# uNav44_r1.net
KiCad netlist of a schematic drawn in EAGLE
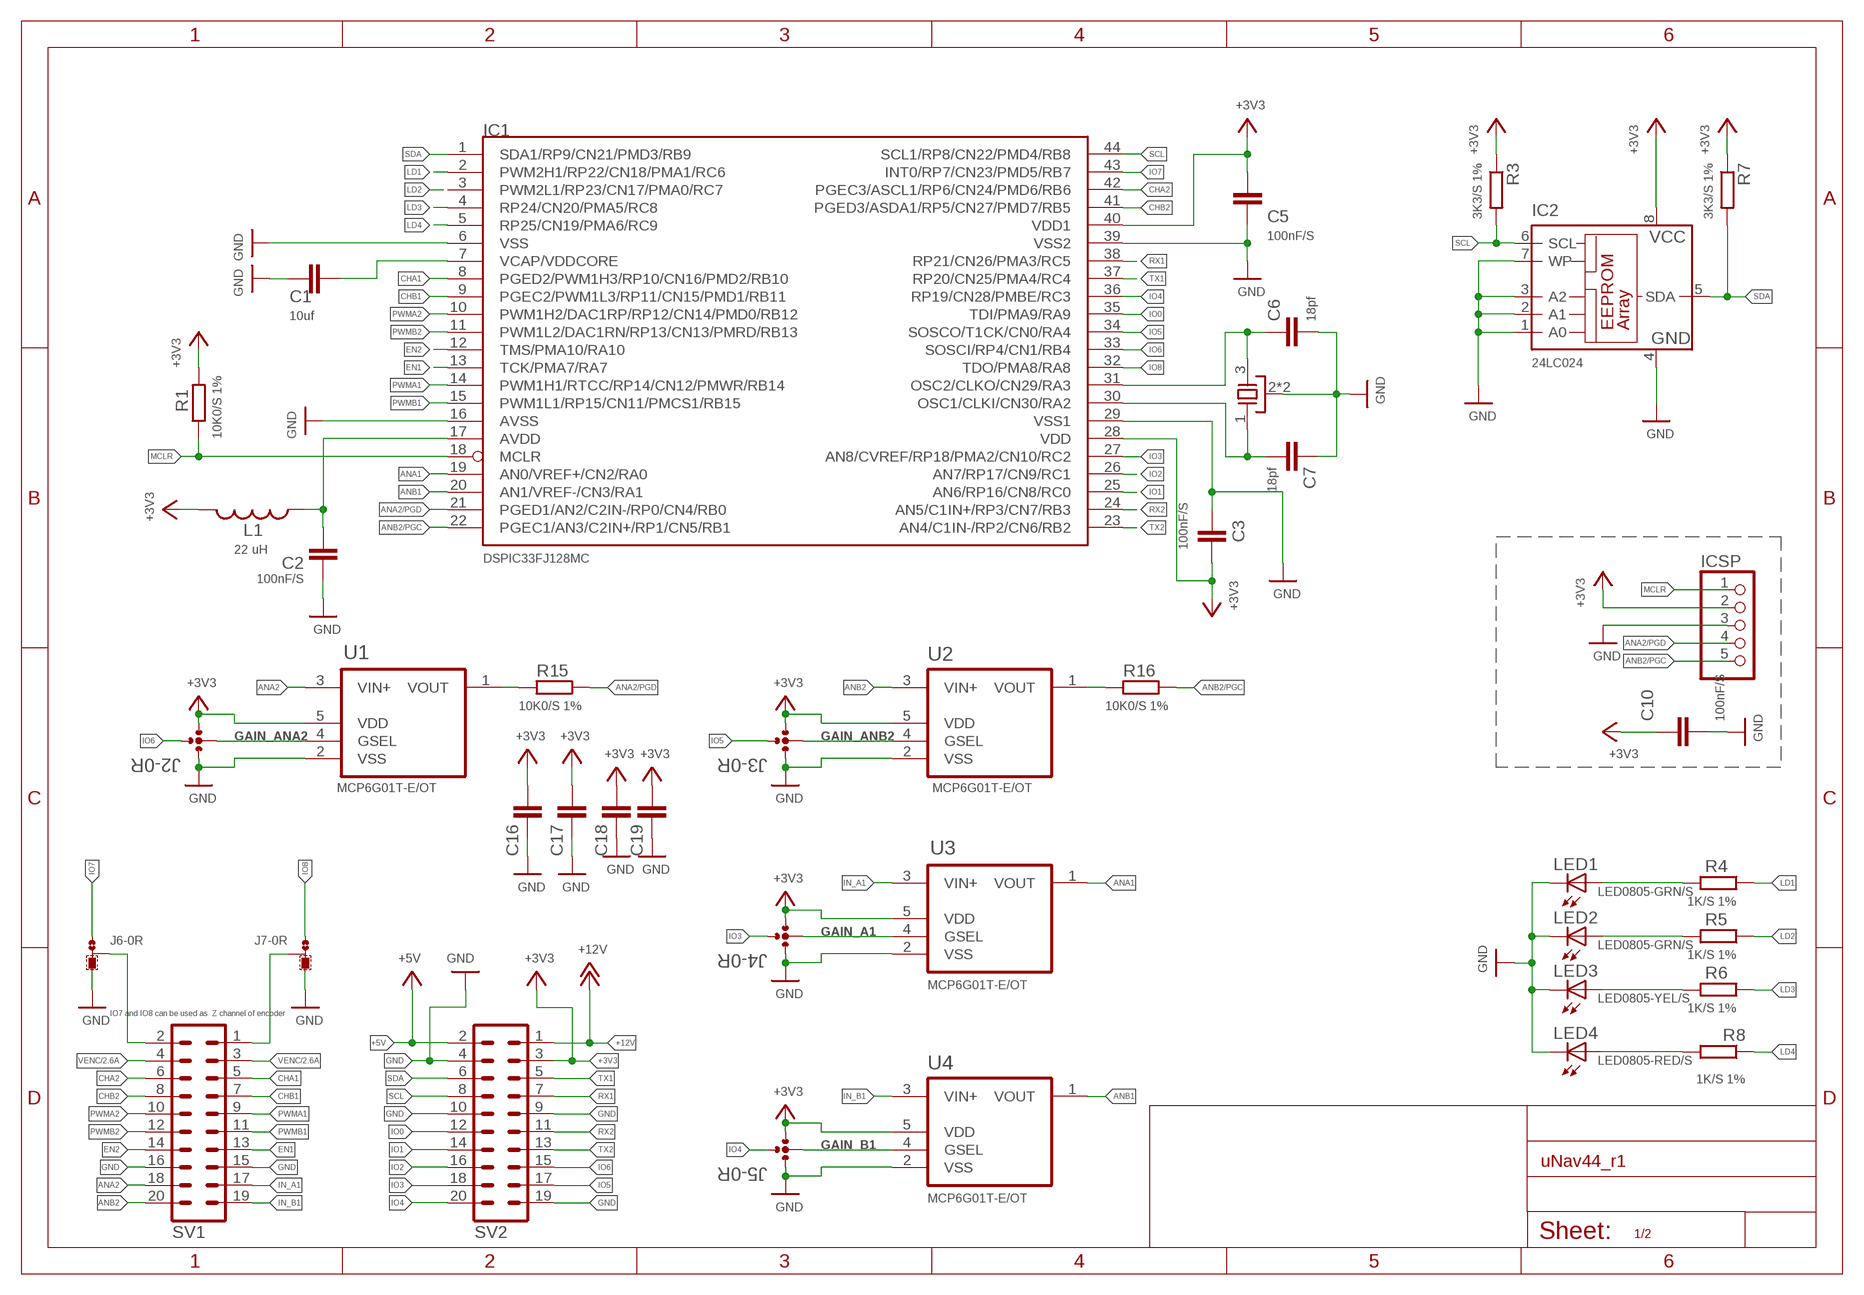
[diagram p0: schematic, sheet 1]
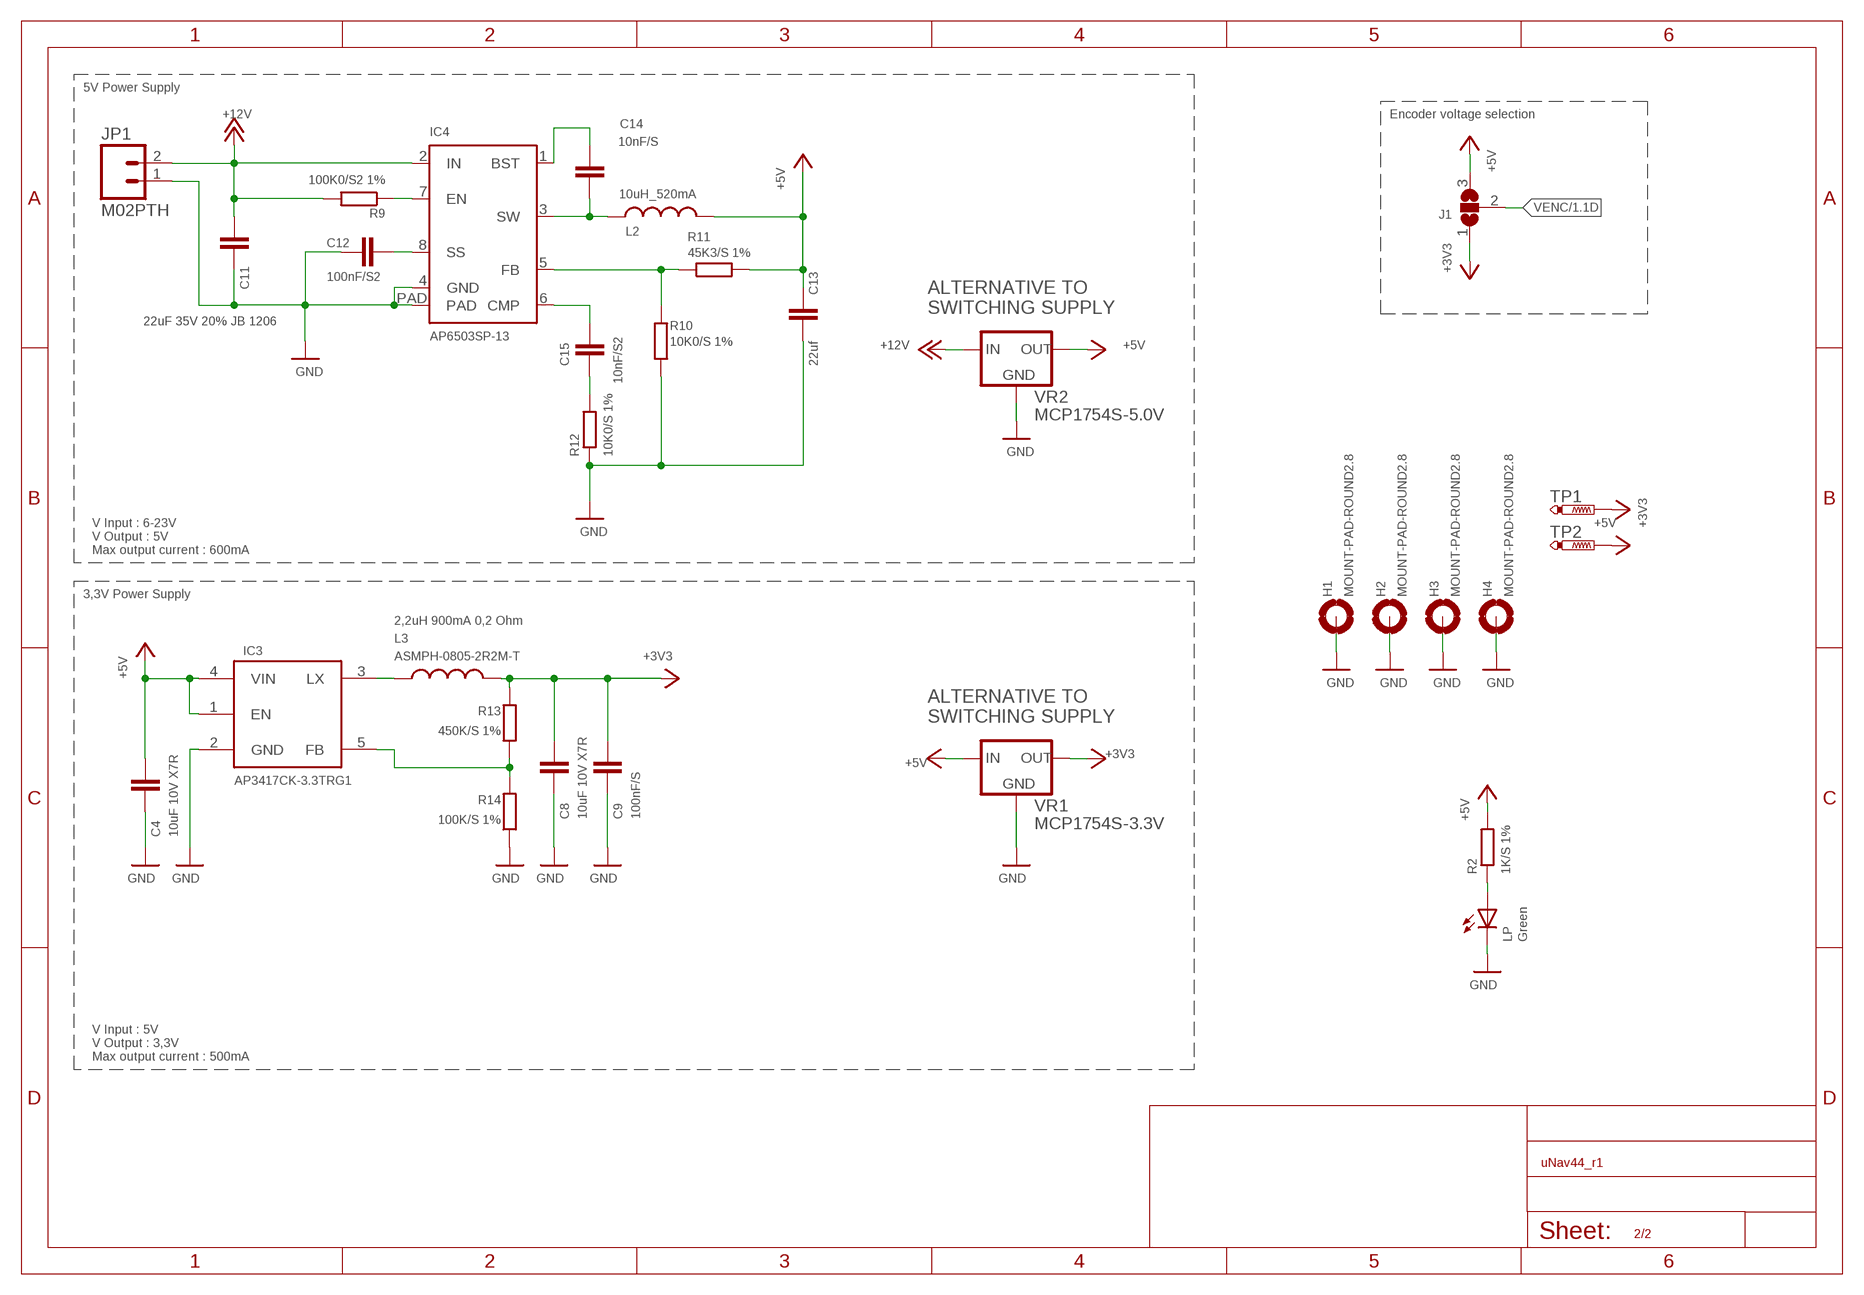
[diagram p1: schematic, sheet 2]

(export (version "E")
  (design (tool "Eeschema 10.0.6"))
  (components
    (comp (ref "C1")
      (value "10uf")
      (footprint "eagle-import:C1206")
      (libsource (lib "eagle-import") (part "C-EUC1206"))
    )
    (comp (ref "C2")
      (value "100nF/S")
      (footprint "eagle-import:C0603")
      (libsource (lib "eagle-import") (part "C-EUC0603"))
    )
    (comp (ref "C3")
      (value "100nF/S")
      (footprint "eagle-import:C0603")
      (libsource (lib "eagle-import") (part "C-EUC0603"))
    )
    (comp (ref "C5")
      (value "100nF/S")
      (footprint "eagle-import:C0603")
      (libsource (lib "eagle-import") (part "C-EUC0603"))
    )
    (comp (ref "C6")
      (value "18pf")
      (footprint "eagle-import:C0603")
      (libsource (lib "eagle-import") (part "C-EUC0603"))
    )
    (comp (ref "C7")
      (value "18pf")
      (footprint "eagle-import:C0603")
      (libsource (lib "eagle-import") (part "C-EUC0603"))
    )
    (comp (ref "C10")
      (value "100nF/S")
      (footprint "eagle-import:C0603")
      (libsource (lib "eagle-import") (part "C-EUC0603"))
    )
    (comp (ref "C16")
      (value "100nF/S")
      (footprint "eagle-import:C0603")
      (libsource (lib "eagle-import") (part "C-EUC0603"))
    )
    (comp (ref "C17")
      (value "100nF/S")
      (footprint "eagle-import:C0603")
      (libsource (lib "eagle-import") (part "C-EUC0603"))
    )
    (comp (ref "C18")
      (value "100nF/S")
      (footprint "eagle-import:C0603")
      (libsource (lib "eagle-import") (part "C-EUC0603"))
    )
    (comp (ref "C19")
      (value "100nF/S")
      (footprint "eagle-import:C0603")
      (libsource (lib "eagle-import") (part "C-EUC0603"))
    )
    (comp (ref "IC1")
      (value "DSPIC33FJ128MC")
      (footprint "eagle-import:TQFP44")
      (libsource (lib "eagle-import") (part "DSPIC33FJ128MC804-PT"))
    )
    (comp (ref "IC2")
      (value "24LC024")
      (footprint "eagle-import:SO-08M")
      (libsource (lib "eagle-import") (part "24SMAA01"))
    )
    (comp (ref "ICSP")
      (value "PINHD-1X05_2.54-S")
      (footprint "eagle-import:1X05-S")
      (libsource (lib "eagle-import") (part "PINHD-1X05_2.54-S"))
    )
    (comp (ref "J2")
      (value "0R-JUMP-4")
      (footprint "eagle-import:C0R-JUMP-4")
      (libsource (lib "eagle-import") (part "0R-JUMP-4"))
    )
    (comp (ref "J3")
      (value "0R-JUMP-4")
      (footprint "eagle-import:C0R-JUMP-4")
      (libsource (lib "eagle-import") (part "0R-JUMP-4"))
    )
    (comp (ref "J4")
      (value "0R-JUMP-4")
      (footprint "eagle-import:C0R-JUMP-4")
      (libsource (lib "eagle-import") (part "0R-JUMP-4"))
    )
    (comp (ref "J5")
      (value "0R-JUMP-4")
      (footprint "eagle-import:C0R-JUMP-4")
      (libsource (lib "eagle-import") (part "0R-JUMP-4"))
    )
    (comp (ref "J6")
      (value "0R-JUMPC")
      (footprint "eagle-import:C0R-JMP")
      (libsource (lib "eagle-import") (part "0R-JUMPC"))
    )
    (comp (ref "J7")
      (value "0R-JUMPC")
      (footprint "eagle-import:C0R-JMP")
      (libsource (lib "eagle-import") (part "0R-JUMPC"))
    )
    (comp (ref "L1")
      (value "22 uH")
      (footprint "eagle-import:0805")
      (libsource (lib "eagle-import") (part "INDUCTOR0805"))
    )
    (comp (ref "LED1")
      (value "LED0805-GRN/S")
      (footprint "eagle-import:CHIPLED_0805")
      (libsource (lib "eagle-import") (part "LEDCHIPLED_0805"))
    )
    (comp (ref "LED2")
      (value "LED0805-GRN/S")
      (footprint "eagle-import:CHIPLED_0805")
      (libsource (lib "eagle-import") (part "LEDCHIPLED_0805"))
    )
    (comp (ref "LED3")
      (value "LED0805-YEL/S")
      (footprint "eagle-import:CHIPLED_0805")
      (libsource (lib "eagle-import") (part "LEDCHIPLED_0805"))
    )
    (comp (ref "LED4")
      (value "LED0805-RED/S")
      (footprint "eagle-import:CHIPLED_0805")
      (libsource (lib "eagle-import") (part "LEDCHIPLED_0805"))
    )
    (comp (ref "R1")
      (value "10K0/S 1%")
      (footprint "eagle-import:R0603")
      (libsource (lib "eagle-import") (part "R-EU_R0603"))
    )
    (comp (ref "R3")
      (value "3K3/S 1%")
      (footprint "eagle-import:R0603")
      (libsource (lib "eagle-import") (part "R-EU_R0603"))
    )
    (comp (ref "R4")
      (value "1K/S 1%")
      (footprint "eagle-import:R0603")
      (libsource (lib "eagle-import") (part "R-EU_R0603"))
    )
    (comp (ref "R5")
      (value "1K/S 1%")
      (footprint "eagle-import:R0603")
      (libsource (lib "eagle-import") (part "R-EU_R0603"))
    )
    (comp (ref "R6")
      (value "1K/S 1%")
      (footprint "eagle-import:R0603")
      (libsource (lib "eagle-import") (part "R-EU_R0603"))
    )
    (comp (ref "R7")
      (value "3K3/S 1%")
      (footprint "eagle-import:R0603")
      (libsource (lib "eagle-import") (part "R-EU_R0603"))
    )
    (comp (ref "R8")
      (value "1K/S 1%")
      (footprint "eagle-import:R0603")
      (libsource (lib "eagle-import") (part "R-EU_R0603"))
    )
    (comp (ref "R15")
      (value "10K0/S 1%")
      (footprint "eagle-import:R0603")
      (libsource (lib "eagle-import") (part "R-EU_R0603"))
    )
    (comp (ref "R16")
      (value "10K0/S 1%")
      (footprint "eagle-import:R0603")
      (libsource (lib "eagle-import") (part "R-EU_R0603"))
    )
    (comp (ref "SV1")
      (value "MA10-2")
      (footprint "eagle-import:MA10-2")
      (fields (field (name "OC_FARNELL") "unknown") (field (name "OC_NEWARK") "unknown"))
      (libsource (lib "eagle-import") (part "MA10-2"))
    )
    (comp (ref "SV2")
      (value "MA10-2")
      (footprint "eagle-import:MA10-2")
      (libsource (lib "eagle-import") (part "MA10-2"))
    )
    (comp (ref "U1")
      (value "MCP6G01T-E/OT")
      (footprint "eagle-import:SOT95P300X145-5N")
      (libsource (lib "eagle-import") (part "MCP6G01T-E/OT"))
    )
    (comp (ref "U2")
      (value "MCP6G01T-E/OT")
      (footprint "eagle-import:SOT95P300X145-5N")
      (libsource (lib "eagle-import") (part "MCP6G01T-E/OT"))
    )
    (comp (ref "U3")
      (value "MCP6G01T-E/OT")
      (footprint "eagle-import:SOT95P300X145-5N")
      (libsource (lib "eagle-import") (part "MCP6G01T-E/OT"))
    )
    (comp (ref "U4")
      (value "MCP6G01T-E/OT")
      (footprint "eagle-import:SOT95P300X145-5N")
      (libsource (lib "eagle-import") (part "MCP6G01T-E/OT"))
    )
    (comp (ref "XT1")
      (value "CTS_32X25_SMD")
      (footprint "eagle-import:CTS_32X25")
      (libsource (lib "eagle-import") (part "CTS_32X25_SMD"))
    )
    (comp (ref "C4")
      (value "10uF 10V X7R")
      (footprint "eagle-import:C0805")
      (libsource (lib "eagle-import") (part "C-EUC0805"))
    )
    (comp (ref "C8")
      (value "10uF 10V X7R")
      (footprint "eagle-import:C0805")
      (libsource (lib "eagle-import") (part "C-EUC0805"))
    )
    (comp (ref "C9")
      (value "100nF/S")
      (footprint "eagle-import:C0603")
      (libsource (lib "eagle-import") (part "C-EUC0603"))
    )
    (comp (ref "C11")
      (value "22uF 35V 20% JB 1206")
      (footprint "eagle-import:C1206")
      (libsource (lib "eagle-import") (part "C-EUC1206"))
    )
    (comp (ref "C12")
      (value "100nF/S2")
      (footprint "eagle-import:C0603")
      (libsource (lib "eagle-import") (part "C-EUC0603"))
    )
    (comp (ref "C13")
      (value "22uf")
      (footprint "eagle-import:C1206")
      (libsource (lib "eagle-import") (part "C-EUC1206"))
    )
    (comp (ref "C14")
      (value "10nF/S")
      (footprint "eagle-import:C0603")
      (libsource (lib "eagle-import") (part "C-EUC0603"))
    )
    (comp (ref "C15")
      (value "10nF/S2")
      (footprint "eagle-import:C0603")
      (libsource (lib "eagle-import") (part "C-EUC0603"))
    )
    (comp (ref "H1")
      (value "MOUNT-PAD-ROUND2.8")
      (footprint "eagle-import:2,8-PAD")
      (libsource (lib "eagle-import") (part "MOUNT-PAD-ROUND2.8"))
    )
    (comp (ref "H2")
      (value "MOUNT-PAD-ROUND2.8")
      (footprint "eagle-import:2,8-PAD")
      (libsource (lib "eagle-import") (part "MOUNT-PAD-ROUND2.8"))
    )
    (comp (ref "H3")
      (value "MOUNT-PAD-ROUND2.8")
      (footprint "eagle-import:2,8-PAD")
      (libsource (lib "eagle-import") (part "MOUNT-PAD-ROUND2.8"))
    )
    (comp (ref "H4")
      (value "MOUNT-PAD-ROUND2.8")
      (footprint "eagle-import:2,8-PAD")
      (libsource (lib "eagle-import") (part "MOUNT-PAD-ROUND2.8"))
    )
    (comp (ref "IC3")
      (value "AP3417CK-3.3TRG1")
      (footprint "eagle-import:SOT-23-5")
      (libsource (lib "eagle-import") (part "AP3417CSOT-23-5"))
    )
    (comp (ref "IC4")
      (value "AP6503SP-13")
      (footprint "eagle-import:SO-8EP")
      (libsource (lib "eagle-import") (part "AP6503SP-13'SO-8EP'"))
    )
    (comp (ref "J1")
      (value "SJ2W")
      (footprint "eagle-import:SJ_2")
      (libsource (lib "eagle-import") (part "SJ2W"))
    )
    (comp (ref "JP1")
      (value "M02PTH")
      (footprint "eagle-import:1X02")
      (libsource (lib "eagle-import") (part "M02PTH"))
    )
    (comp (ref "L2")
      (value "10uH_520mA")
      (footprint "eagle-import:1210")
      (libsource (lib "eagle-import") (part "INDUCTOR1210"))
    )
    (comp (ref "L3")
      (value "ASMPH-0805-2R2M-T")
      (footprint "eagle-import:0805")
      (libsource (lib "eagle-import") (part "INDUCTOR0805"))
    )
    (comp (ref "LP")
      (value "Green")
      (footprint "eagle-import:CHIPLED_0805")
      (libsource (lib "eagle-import") (part "LEDCHIPLED_0805"))
    )
    (comp (ref "R2")
      (value "1K/S 1%")
      (footprint "eagle-import:R0603")
      (libsource (lib "eagle-import") (part "R-EU_R0603"))
    )
    (comp (ref "R9")
      (value "100K0/S2 1%")
      (footprint "eagle-import:R0603")
      (libsource (lib "eagle-import") (part "R-EU_R0603"))
    )
    (comp (ref "R10")
      (value "10K0/S 1%")
      (footprint "eagle-import:R0603")
      (libsource (lib "eagle-import") (part "R-EU_R0603"))
    )
    (comp (ref "R11")
      (value "45K3/S 1%")
      (footprint "eagle-import:R0603")
      (libsource (lib "eagle-import") (part "R-EU_R0603"))
    )
    (comp (ref "R12")
      (value "10K0/S 1%")
      (footprint "eagle-import:R0603")
      (libsource (lib "eagle-import") (part "R-EU_R0603"))
    )
    (comp (ref "R13")
      (value "450K/S 1%")
      (footprint "eagle-import:R0603")
      (libsource (lib "eagle-import") (part "R-EU_R0603"))
    )
    (comp (ref "R14")
      (value "100K/S 1%")
      (footprint "eagle-import:R0603")
      (libsource (lib "eagle-import") (part "R-EU_R0603"))
    )
    (comp (ref "TP1")
      (value "PTR1TP07R")
      (footprint "eagle-import:TP07R")
      (libsource (lib "eagle-import") (part "PTR1TP07R"))
    )
    (comp (ref "TP2")
      (value "PTR1TP07R")
      (footprint "eagle-import:TP07R")
      (libsource (lib "eagle-import") (part "PTR1TP07R"))
    )
    (comp (ref "VR1")
      (value "MCP1754S-3.3V")
      (footprint "eagle-import:SOT89")
      (libsource (lib "eagle-import") (part "MCP1754S"))
    )
    (comp (ref "VR2")
      (value "MCP1754S-5.0V")
      (footprint "eagle-import:SOT89")
      (libsource (lib "eagle-import") (part "MCP1754S"))
    )
  )
  (nets
    (net (code "1") (name "+3V3") (class "Default")
      (node (ref "C10") (pin "1") (pinfunction "1_1") (pintype "passive"))
      (node (ref "C16") (pin "1") (pinfunction "1_1") (pintype "passive"))
      (node (ref "C17") (pin "1") (pinfunction "1_1") (pintype "passive"))
      (node (ref "C18") (pin "1") (pinfunction "1_1") (pintype "passive"))
      (node (ref "C19") (pin "1") (pinfunction "1_1") (pintype "passive"))
      (node (ref "C3") (pin "1") (pinfunction "1_1") (pintype "passive"))
      (node (ref "C5") (pin "2") (pinfunction "2_2") (pintype "passive"))
      (node (ref "C8") (pin "1") (pinfunction "1_1") (pintype "passive"))
      (node (ref "C9") (pin "1") (pinfunction "1_1") (pintype "passive"))
      (node (ref "IC1") (pin "28") (pinfunction "VDD_28") (pintype "power_in"))
      (node (ref "IC1") (pin "40") (pinfunction "VDD1_40") (pintype "power_in"))
      (node (ref "IC2") (pin "8") (pinfunction "VCC_8") (pintype "power_in"))
      (node (ref "ICSP") (pin "2") (pinfunction "2_2") (pintype "passive"))
      (node (ref "J1") (pin "1") (pinfunction "1_1") (pintype "passive"))
      (node (ref "J2") (pin "1") (pinfunction "1_1") (pintype "passive"))
      (node (ref "J3") (pin "1") (pinfunction "1_1") (pintype "passive"))
      (node (ref "J4") (pin "1") (pinfunction "1_1") (pintype "passive"))
      (node (ref "J5") (pin "1") (pinfunction "1_1") (pintype "passive"))
      (node (ref "L1") (pin "2") (pinfunction "2_2") (pintype "passive"))
      (node (ref "L3") (pin "2") (pinfunction "2_2") (pintype "passive"))
      (node (ref "R1") (pin "2") (pinfunction "2_2") (pintype "passive"))
      (node (ref "R13") (pin "2") (pinfunction "2_2") (pintype "passive"))
      (node (ref "R3") (pin "1") (pinfunction "1_1") (pintype "passive"))
      (node (ref "R7") (pin "1") (pinfunction "1_1") (pintype "passive"))
      (node (ref "SV2") (pin "3") (pinfunction "3_3") (pintype "passive"))
      (node (ref "TP1") (pin "TP") (pinfunction "TP_TP") (pintype "input"))
      (node (ref "U1") (pin "5") (pinfunction "VDD_5") (pintype "power_in"))
      (node (ref "U2") (pin "5") (pinfunction "VDD_5") (pintype "power_in"))
      (node (ref "U3") (pin "5") (pinfunction "VDD_5") (pintype "power_in"))
      (node (ref "U4") (pin "5") (pinfunction "VDD_5") (pintype "power_in"))
      (node (ref "VR1") (pin "3") (pinfunction "OUT_3") (pintype "passive"))
    )
    (net (code "2") (name "+5V") (class "Default")
      (node (ref "C13") (pin "1") (pinfunction "1_1") (pintype "passive"))
      (node (ref "C4") (pin "1") (pinfunction "1_1") (pintype "passive"))
      (node (ref "IC3") (pin "1") (pinfunction "EN_1") (pintype "bidirectional"))
      (node (ref "IC3") (pin "4") (pinfunction "VIN_4") (pintype "bidirectional"))
      (node (ref "J1") (pin "3") (pinfunction "3_3") (pintype "passive"))
      (node (ref "L2") (pin "2") (pinfunction "2_2") (pintype "passive"))
      (node (ref "R11") (pin "2") (pinfunction "2_2") (pintype "passive"))
      (node (ref "R2") (pin "2") (pinfunction "2_2") (pintype "passive"))
      (node (ref "SV2") (pin "2") (pinfunction "2_2") (pintype "passive"))
      (node (ref "TP2") (pin "TP") (pinfunction "TP_TP") (pintype "input"))
      (node (ref "VR1") (pin "1") (pinfunction "IN_1") (pintype "input"))
      (node (ref "VR2") (pin "3") (pinfunction "OUT_3") (pintype "passive"))
    )
    (net (code "3") (name "+12V") (class "Default")
      (node (ref "C11") (pin "1") (pinfunction "1_1") (pintype "passive"))
      (node (ref "IC4") (pin "2") (pinfunction "IN_2") (pintype "power_in"))
      (node (ref "JP1") (pin "2") (pinfunction "2_2") (pintype "passive"))
      (node (ref "R9") (pin "2") (pinfunction "2_2") (pintype "passive"))
      (node (ref "SV2") (pin "1") (pinfunction "1_1") (pintype "passive"))
      (node (ref "VR2") (pin "1") (pinfunction "IN_1") (pintype "input"))
    )
    (net (code "4") (name "ANA1") (class "Default")
      (node (ref "IC1") (pin "19") (pinfunction "AN0/VREF+/CN2/RA0_19") (pintype "bidirectional"))
      (node (ref "U3") (pin "1") (pinfunction "VOUT_1") (pintype "output"))
    )
    (net (code "5") (name "ANA2") (class "Default")
      (node (ref "SV1") (pin "18") (pinfunction "18_18") (pintype "passive"))
      (node (ref "U1") (pin "3") (pinfunction "VIN+_3") (pintype "input"))
    )
    (net (code "6") (name "ANA2{slash}PGD") (class "Default")
      (node (ref "IC1") (pin "21") (pinfunction "PGED1/AN2/C2IN-/RP0/CN4/RB0_21") (pintype "bidirectional"))
      (node (ref "ICSP") (pin "4") (pinfunction "4_4") (pintype "passive"))
      (node (ref "R15") (pin "1") (pinfunction "1_1") (pintype "passive"))
    )
    (net (code "7") (name "ANB1") (class "Default")
      (node (ref "IC1") (pin "20") (pinfunction "AN1/VREF-/CN3/RA1_20") (pintype "bidirectional"))
      (node (ref "U4") (pin "1") (pinfunction "VOUT_1") (pintype "output"))
    )
    (net (code "8") (name "ANB2") (class "Default")
      (node (ref "SV1") (pin "20") (pinfunction "20_20") (pintype "passive"))
      (node (ref "U2") (pin "3") (pinfunction "VIN+_3") (pintype "input"))
    )
    (net (code "9") (name "ANB2{slash}PGC") (class "Default")
      (node (ref "IC1") (pin "22") (pinfunction "PGEC1/AN3/C2IN+/RP1/CN5/RB1_22") (pintype "bidirectional"))
      (node (ref "ICSP") (pin "5") (pinfunction "5_5") (pintype "passive"))
      (node (ref "R16") (pin "1") (pinfunction "1_1") (pintype "passive"))
    )
    (net (code "10") (name "CHA1") (class "Default")
      (node (ref "IC1") (pin "8") (pinfunction "PGED2/PWM1H3/RP10/CN16/PMD2/RB10_8") (pintype "bidirectional"))
      (node (ref "SV1") (pin "5") (pinfunction "5_5") (pintype "passive"))
    )
    (net (code "11") (name "CHA2") (class "Default")
      (node (ref "IC1") (pin "42") (pinfunction "PGEC3/ASCL1/RP6/CN24/PMD6/RB6_42") (pintype "bidirectional"))
      (node (ref "SV1") (pin "6") (pinfunction "6_6") (pintype "passive"))
    )
    (net (code "12") (name "CHB1") (class "Default")
      (node (ref "IC1") (pin "9") (pinfunction "PGEC2/PWM1L3/RP11/CN15/PMD1/RB11_9") (pintype "bidirectional"))
      (node (ref "SV1") (pin "7") (pinfunction "7_7") (pintype "passive"))
    )
    (net (code "13") (name "CHB2") (class "Default")
      (node (ref "IC1") (pin "41") (pinfunction "PGED3/ASDA1/RP5/CN27/PMD7/RB5_41") (pintype "bidirectional"))
      (node (ref "SV1") (pin "8") (pinfunction "8_8") (pintype "passive"))
    )
    (net (code "14") (name "EN1") (class "Default")
      (node (ref "IC1") (pin "13") (pinfunction "TCK/PMA7/RA7_13") (pintype "bidirectional"))
      (node (ref "SV1") (pin "13") (pinfunction "13_13") (pintype "passive"))
    )
    (net (code "15") (name "EN2") (class "Default")
      (node (ref "IC1") (pin "12") (pinfunction "TMS/PMA10/RA10_12") (pintype "bidirectional"))
      (node (ref "SV1") (pin "14") (pinfunction "14_14") (pintype "passive"))
    )
    (net (code "16") (name "GAIN_A1") (class "Default")
      (node (ref "J4") (pin "2") (pinfunction "2_2") (pintype "passive"))
      (node (ref "U3") (pin "4") (pinfunction "GSEL_4") (pintype "input"))
    )
    (net (code "17") (name "GAIN_ANA2") (class "Default")
      (node (ref "J2") (pin "2") (pinfunction "2_2") (pintype "passive"))
      (node (ref "U1") (pin "4") (pinfunction "GSEL_4") (pintype "input"))
    )
    (net (code "18") (name "GAIN_ANB2") (class "Default")
      (node (ref "J3") (pin "2") (pinfunction "2_2") (pintype "passive"))
      (node (ref "U2") (pin "4") (pinfunction "GSEL_4") (pintype "input"))
    )
    (net (code "19") (name "GAIN_B1") (class "Default")
      (node (ref "J5") (pin "2") (pinfunction "2_2") (pintype "passive"))
      (node (ref "U4") (pin "4") (pinfunction "GSEL_4") (pintype "input"))
    )
    (net (code "20") (name "GND") (class "Default")
      (node (ref "C1") (pin "2") (pinfunction "2_2") (pintype "passive"))
      (node (ref "C10") (pin "2") (pinfunction "2_2") (pintype "passive"))
      (node (ref "C11") (pin "2") (pinfunction "2_2") (pintype "passive"))
      (node (ref "C12") (pin "2") (pinfunction "2_2") (pintype "passive"))
      (node (ref "C13") (pin "2") (pinfunction "2_2") (pintype "passive"))
      (node (ref "C16") (pin "2") (pinfunction "2_2") (pintype "passive"))
      (node (ref "C17") (pin "2") (pinfunction "2_2") (pintype "passive"))
      (node (ref "C18") (pin "2") (pinfunction "2_2") (pintype "passive"))
      (node (ref "C19") (pin "2") (pinfunction "2_2") (pintype "passive"))
      (node (ref "C2") (pin "1") (pinfunction "1_1") (pintype "passive"))
      (node (ref "C3") (pin "2") (pinfunction "2_2") (pintype "passive"))
      (node (ref "C4") (pin "2") (pinfunction "2_2") (pintype "passive"))
      (node (ref "C5") (pin "1") (pinfunction "1_1") (pintype "passive"))
      (node (ref "C6") (pin "2") (pinfunction "2_2") (pintype "passive"))
      (node (ref "C7") (pin "1") (pinfunction "1_1") (pintype "passive"))
      (node (ref "C8") (pin "2") (pinfunction "2_2") (pintype "passive"))
      (node (ref "C9") (pin "2") (pinfunction "2_2") (pintype "passive"))
      (node (ref "H1") (pin "B2,8") (pinfunction "MOUNT_B2,8") (pintype "passive"))
      (node (ref "H2") (pin "B2,8") (pinfunction "MOUNT_B2,8") (pintype "passive"))
      (node (ref "H3") (pin "B2,8") (pinfunction "MOUNT_B2,8") (pintype "passive"))
      (node (ref "H4") (pin "B2,8") (pinfunction "MOUNT_B2,8") (pintype "passive"))
      (node (ref "IC1") (pin "16") (pinfunction "AVSS_16") (pintype "power_in"))
      (node (ref "IC1") (pin "29") (pinfunction "VSS1_29") (pintype "power_in"))
      (node (ref "IC1") (pin "39") (pinfunction "VSS2_39") (pintype "power_in"))
      (node (ref "IC1") (pin "6") (pinfunction "VSS_6") (pintype "power_in"))
      (node (ref "IC2") (pin "1") (pinfunction "A0_1") (pintype "input"))
      (node (ref "IC2") (pin "2") (pinfunction "A1_2") (pintype "input"))
      (node (ref "IC2") (pin "3") (pinfunction "A2_3") (pintype "input"))
      (node (ref "IC2") (pin "4") (pinfunction "GND_4") (pintype "power_in"))
      (node (ref "IC2") (pin "7") (pinfunction "WP_7") (pintype "input"))
      (node (ref "IC3") (pin "2") (pinfunction "GND_2") (pintype "bidirectional"))
      (node (ref "IC4") (pin "4") (pinfunction "GND_4") (pintype "power_in"))
      (node (ref "IC4") (pin "PAD") (pinfunction "PAD_PAD") (pintype "power_in"))
      (node (ref "ICSP") (pin "3") (pinfunction "3_3") (pintype "passive"))
      (node (ref "J2") (pin "3") (pinfunction "3_3") (pintype "passive"))
      (node (ref "J3") (pin "3") (pinfunction "3_3") (pintype "passive"))
      (node (ref "J4") (pin "3") (pinfunction "3_3") (pintype "passive"))
      (node (ref "J5") (pin "3") (pinfunction "3_3") (pintype "passive"))
      (node (ref "J6") (pin "3") (pinfunction "3_3") (pintype "passive"))
      (node (ref "J7") (pin "3") (pinfunction "3_3") (pintype "passive"))
      (node (ref "JP1") (pin "1") (pinfunction "1_1") (pintype "passive"))
      (node (ref "LED1") (pin "C") (pinfunction "C_C") (pintype "passive"))
      (node (ref "LED2") (pin "C") (pinfunction "C_C") (pintype "passive"))
      (node (ref "LED3") (pin "C") (pinfunction "C_C") (pintype "passive"))
      (node (ref "LED4") (pin "C") (pinfunction "C_C") (pintype "passive"))
      (node (ref "LP") (pin "C") (pinfunction "C_C") (pintype "passive"))
      (node (ref "R10") (pin "2") (pinfunction "2_2") (pintype "passive"))
      (node (ref "R12") (pin "1") (pinfunction "1_1") (pintype "passive"))
      (node (ref "R14") (pin "1") (pinfunction "1_1") (pintype "passive"))
      (node (ref "SV1") (pin "15") (pinfunction "15_15") (pintype "passive"))
      (node (ref "SV1") (pin "16") (pinfunction "16_16") (pintype "passive"))
      (node (ref "SV2") (pin "10") (pinfunction "10_10") (pintype "passive"))
      (node (ref "SV2") (pin "19") (pinfunction "19_19") (pintype "passive"))
      (node (ref "SV2") (pin "4") (pinfunction "4_4") (pintype "passive"))
      (node (ref "SV2") (pin "9") (pinfunction "9_9") (pintype "passive"))
      (node (ref "U1") (pin "2") (pinfunction "VSS_2") (pintype "passive"))
      (node (ref "U2") (pin "2") (pinfunction "VSS_2") (pintype "passive"))
      (node (ref "U3") (pin "2") (pinfunction "VSS_2") (pintype "passive"))
      (node (ref "U4") (pin "2") (pinfunction "VSS_2") (pintype "passive"))
      (node (ref "VR1") (pin "2") (pinfunction "GND_2") (pintype "input"))
      (node (ref "VR1") (pin "4") (pinfunction "GND_4") (pintype "input"))
      (node (ref "VR2") (pin "2") (pinfunction "GND_2") (pintype "input"))
      (node (ref "VR2") (pin "4") (pinfunction "GND_4") (pintype "input"))
      (node (ref "XT1") (pin "2") (pinfunction "GND_2") (pintype "power_in"))
      (node (ref "XT1") (pin "4") (pinfunction "GND_4") (pintype "power_in"))
    )
    (net (code "21") (name "IN_A1") (class "Default")
      (node (ref "SV1") (pin "17") (pinfunction "17_17") (pintype "passive"))
      (node (ref "U3") (pin "3") (pinfunction "VIN+_3") (pintype "input"))
    )
    (net (code "22") (name "IN_B1") (class "Default")
      (node (ref "SV1") (pin "19") (pinfunction "19_19") (pintype "passive"))
      (node (ref "U4") (pin "3") (pinfunction "VIN+_3") (pintype "input"))
    )
    (net (code "23") (name "IO0") (class "Default")
      (node (ref "IC1") (pin "35") (pinfunction "TDI/PMA9/RA9_35") (pintype "bidirectional"))
      (node (ref "SV2") (pin "12") (pinfunction "12_12") (pintype "passive"))
    )
    (net (code "24") (name "IO1") (class "Default")
      (node (ref "IC1") (pin "25") (pinfunction "AN6/RP16/CN8/RC0_25") (pintype "bidirectional"))
      (node (ref "SV2") (pin "14") (pinfunction "14_14") (pintype "passive"))
    )
    (net (code "25") (name "IO2") (class "Default")
      (node (ref "IC1") (pin "26") (pinfunction "AN7/RP17/CN9/RC1_26") (pintype "bidirectional"))
      (node (ref "SV2") (pin "16") (pinfunction "16_16") (pintype "passive"))
    )
    (net (code "26") (name "IO3") (class "Default")
      (node (ref "IC1") (pin "27") (pinfunction "AN8/CVREF/RP18/PMA2/CN10/RC2_27") (pintype "bidirectional"))
      (node (ref "J4") (pin "4") (pinfunction "4_4") (pintype "passive"))
      (node (ref "SV2") (pin "18") (pinfunction "18_18") (pintype "passive"))
    )
    (net (code "27") (name "IO4") (class "Default")
      (node (ref "IC1") (pin "36") (pinfunction "RP19/CN28/PMBE/RC3_36") (pintype "bidirectional"))
      (node (ref "J5") (pin "4") (pinfunction "4_4") (pintype "passive"))
      (node (ref "SV2") (pin "20") (pinfunction "20_20") (pintype "passive"))
    )
    (net (code "28") (name "IO5") (class "Default")
      (node (ref "IC1") (pin "34") (pinfunction "SOSCO/T1CK/CN0/RA4_34") (pintype "bidirectional"))
      (node (ref "J3") (pin "4") (pinfunction "4_4") (pintype "passive"))
      (node (ref "SV2") (pin "17") (pinfunction "17_17") (pintype "passive"))
    )
    (net (code "29") (name "IO6") (class "Default")
      (node (ref "IC1") (pin "33") (pinfunction "SOSCI/RP4/CN1/RB4_33") (pintype "bidirectional"))
      (node (ref "J2") (pin "4") (pinfunction "4_4") (pintype "passive"))
      (node (ref "SV2") (pin "15") (pinfunction "15_15") (pintype "passive"))
    )
    (net (code "30") (name "IO7") (class "Default")
      (node (ref "IC1") (pin "43") (pinfunction "INT0/RP7/CN23/PMD5/RB7_43") (pintype "bidirectional"))
      (node (ref "J6") (pin "1") (pinfunction "1_1") (pintype "passive"))
    )
    (net (code "31") (name "IO8") (class "Default")
      (node (ref "IC1") (pin "32") (pinfunction "TDO/PMA8/RA8_32") (pintype "bidirectional"))
      (node (ref "J7") (pin "1") (pinfunction "1_1") (pintype "passive"))
    )
    (net (code "32") (name "LD1") (class "Default")
      (node (ref "IC1") (pin "2") (pinfunction "PWM2H1/RP22/CN18/PMA1/RC6_2") (pintype "bidirectional"))
      (node (ref "R4") (pin "1") (pinfunction "1_1") (pintype "passive"))
    )
    (net (code "33") (name "LD2") (class "Default")
      (node (ref "IC1") (pin "3") (pinfunction "PWM2L1/RP23/CN17/PMA0/RC7_3") (pintype "bidirectional"))
      (node (ref "R5") (pin "1") (pinfunction "1_1") (pintype "passive"))
    )
    (net (code "34") (name "LD3") (class "Default")
      (node (ref "IC1") (pin "4") (pinfunction "RP24/CN20/PMA5/RC8_4") (pintype "bidirectional"))
      (node (ref "R6") (pin "1") (pinfunction "1_1") (pintype "passive"))
    )
    (net (code "35") (name "LD4") (class "Default")
      (node (ref "IC1") (pin "5") (pinfunction "RP25/CN19/PMA6/RC9_5") (pintype "bidirectional"))
      (node (ref "R8") (pin "1") (pinfunction "1_1") (pintype "passive"))
    )
    (net (code "36") (name "MCLR") (class "Default")
      (node (ref "IC1") (pin "18") (pinfunction "MCLR_18") (pintype "input"))
      (node (ref "ICSP") (pin "1") (pinfunction "1_1") (pintype "passive"))
      (node (ref "R1") (pin "1") (pinfunction "1_1") (pintype "passive"))
    )
    (net (code "37") (name "Net-(C15-Pad2)") (class "Default")
      (node (ref "C15") (pin "2") (pinfunction "2_2") (pintype "passive"))
      (node (ref "R12") (pin "2") (pinfunction "2_2") (pintype "passive"))
    )
    (net (code "38") (name "Net-(IC1-AVDD)") (class "Default")
      (node (ref "C2") (pin "2") (pinfunction "2_2") (pintype "passive"))
      (node (ref "IC1") (pin "17") (pinfunction "AVDD_17") (pintype "power_in"))
      (node (ref "L1") (pin "1") (pinfunction "1_1") (pintype "passive"))
    )
    (net (code "39") (name "Net-(IC1-OSC1{slash}CLKI{slash}CN30{slash}RA2)") (class "Default")
      (node (ref "C7") (pin "2") (pinfunction "2_2") (pintype "passive"))
      (node (ref "IC1") (pin "30") (pinfunction "OSC1/CLKI/CN30/RA2_30") (pintype "bidirectional"))
      (node (ref "XT1") (pin "1") (pinfunction "X1_1") (pintype "bidirectional"))
    )
    (net (code "40") (name "Net-(IC1-OSC2{slash}CLKO{slash}CN29{slash}RA3)") (class "Default")
      (node (ref "C6") (pin "1") (pinfunction "1_1") (pintype "passive"))
      (node (ref "IC1") (pin "31") (pinfunction "OSC2/CLKO/CN29/RA3_31") (pintype "bidirectional"))
      (node (ref "XT1") (pin "3") (pinfunction "X2_3") (pintype "bidirectional"))
    )
    (net (code "41") (name "Net-(IC1-VCAP{slash}VDDCORE)") (class "Default")
      (node (ref "C1") (pin "1") (pinfunction "1_1") (pintype "passive"))
      (node (ref "IC1") (pin "7") (pinfunction "VCAP/VDDCORE_7") (pintype "power_in"))
    )
    (net (code "42") (name "Net-(IC3-FB)") (class "Default")
      (node (ref "IC3") (pin "5") (pinfunction "FB_5") (pintype "bidirectional"))
      (node (ref "R13") (pin "1") (pinfunction "1_1") (pintype "passive"))
      (node (ref "R14") (pin "2") (pinfunction "2_2") (pintype "passive"))
    )
    (net (code "43") (name "Net-(IC3-LX)") (class "Default")
      (node (ref "IC3") (pin "3") (pinfunction "LX_3") (pintype "bidirectional"))
      (node (ref "L3") (pin "1") (pinfunction "1_1") (pintype "passive"))
    )
    (net (code "44") (name "Net-(IC4-BST)") (class "Default")
      (node (ref "C14") (pin "1") (pinfunction "1_1") (pintype "passive"))
      (node (ref "IC4") (pin "1") (pinfunction "BST_1") (pintype "bidirectional"))
    )
    (net (code "45") (name "Net-(IC4-CMP)") (class "Default")
      (node (ref "C15") (pin "1") (pinfunction "1_1") (pintype "passive"))
      (node (ref "IC4") (pin "6") (pinfunction "CMP_6") (pintype "bidirectional"))
    )
    (net (code "46") (name "Net-(IC4-EN)") (class "Default")
      (node (ref "IC4") (pin "7") (pinfunction "EN_7") (pintype "bidirectional"))
      (node (ref "R9") (pin "1") (pinfunction "1_1") (pintype "passive"))
    )
    (net (code "47") (name "Net-(IC4-FB)") (class "Default")
      (node (ref "IC4") (pin "5") (pinfunction "FB_5") (pintype "bidirectional"))
      (node (ref "R10") (pin "1") (pinfunction "1_1") (pintype "passive"))
      (node (ref "R11") (pin "1") (pinfunction "1_1") (pintype "passive"))
    )
    (net (code "48") (name "Net-(IC4-SS)") (class "Default")
      (node (ref "C12") (pin "1") (pinfunction "1_1") (pintype "passive"))
      (node (ref "IC4") (pin "8") (pinfunction "SS_8") (pintype "bidirectional"))
    )
    (net (code "49") (name "Net-(IC4-SW)") (class "Default")
      (node (ref "C14") (pin "2") (pinfunction "2_2") (pintype "passive"))
      (node (ref "IC4") (pin "3") (pinfunction "SW_3") (pintype "bidirectional"))
      (node (ref "L2") (pin "1") (pinfunction "1_1") (pintype "passive"))
    )
    (net (code "50") (name "Net-(J6-Pad2)") (class "Default")
      (node (ref "J6") (pin "2") (pinfunction "2_2") (pintype "passive"))
      (node (ref "SV1") (pin "2") (pinfunction "2_2") (pintype "passive"))
    )
    (net (code "51") (name "Net-(J7-Pad2)") (class "Default")
      (node (ref "J7") (pin "2") (pinfunction "2_2") (pintype "passive"))
      (node (ref "SV1") (pin "1") (pinfunction "1_1") (pintype "passive"))
    )
    (net (code "52") (name "Net-(LED1-PadA)") (class "Default")
      (node (ref "LED1") (pin "A") (pinfunction "A_A") (pintype "passive"))
      (node (ref "R4") (pin "2") (pinfunction "2_2") (pintype "passive"))
    )
    (net (code "53") (name "Net-(LED2-PadA)") (class "Default")
      (node (ref "LED2") (pin "A") (pinfunction "A_A") (pintype "passive"))
      (node (ref "R5") (pin "2") (pinfunction "2_2") (pintype "passive"))
    )
    (net (code "54") (name "Net-(LED3-PadA)") (class "Default")
      (node (ref "LED3") (pin "A") (pinfunction "A_A") (pintype "passive"))
      (node (ref "R6") (pin "2") (pinfunction "2_2") (pintype "passive"))
    )
    (net (code "55") (name "Net-(LED4-PadA)") (class "Default")
      (node (ref "LED4") (pin "A") (pinfunction "A_A") (pintype "passive"))
      (node (ref "R8") (pin "2") (pinfunction "2_2") (pintype "passive"))
    )
    (net (code "56") (name "Net-(LP-PadA)") (class "Default")
      (node (ref "LP") (pin "A") (pinfunction "A_A") (pintype "passive"))
      (node (ref "R2") (pin "1") (pinfunction "1_1") (pintype "passive"))
    )
    (net (code "57") (name "Net-(U1-VOUT)") (class "Default")
      (node (ref "R15") (pin "2") (pinfunction "2_2") (pintype "passive"))
      (node (ref "U1") (pin "1") (pinfunction "VOUT_1") (pintype "output"))
    )
    (net (code "58") (name "Net-(U2-VOUT)") (class "Default")
      (node (ref "R16") (pin "2") (pinfunction "2_2") (pintype "passive"))
      (node (ref "U2") (pin "1") (pinfunction "VOUT_1") (pintype "output"))
    )
    (net (code "59") (name "PWMA1") (class "Default")
      (node (ref "IC1") (pin "14") (pinfunction "PWM1H1/RTCC/RP14/CN12/PMWR/RB14_14") (pintype "bidirectional"))
      (node (ref "SV1") (pin "9") (pinfunction "9_9") (pintype "passive"))
    )
    (net (code "60") (name "PWMA2") (class "Default")
      (node (ref "IC1") (pin "10") (pinfunction "PWM1H2/DAC1RP/RP12/CN14/PMD0/RB12_10") (pintype "bidirectional"))
      (node (ref "SV1") (pin "10") (pinfunction "10_10") (pintype "passive"))
    )
    (net (code "61") (name "PWMB1") (class "Default")
      (node (ref "IC1") (pin "15") (pinfunction "PWM1L1/RP15/CN11/PMCS1/RB15_15") (pintype "bidirectional"))
      (node (ref "SV1") (pin "11") (pinfunction "11_11") (pintype "passive"))
    )
    (net (code "62") (name "PWMB2") (class "Default")
      (node (ref "IC1") (pin "11") (pinfunction "PWM1L2/DAC1RN/RP13/CN13/PMRD/RB13_11") (pintype "bidirectional"))
      (node (ref "SV1") (pin "12") (pinfunction "12_12") (pintype "passive"))
    )
    (net (code "63") (name "RX1") (class "Default")
      (node (ref "IC1") (pin "38") (pinfunction "RP21/CN26/PMA3/RC5_38") (pintype "bidirectional"))
      (node (ref "SV2") (pin "7") (pinfunction "7_7") (pintype "passive"))
    )
    (net (code "64") (name "RX2") (class "Default")
      (node (ref "IC1") (pin "24") (pinfunction "AN5/C1IN+/RP3/CN7/RB3_24") (pintype "bidirectional"))
      (node (ref "SV2") (pin "11") (pinfunction "11_11") (pintype "passive"))
    )
    (net (code "65") (name "SCL") (class "Default")
      (node (ref "IC1") (pin "44") (pinfunction "SCL1/RP8/CN22/PMD4/RB8_44") (pintype "bidirectional"))
      (node (ref "IC2") (pin "6") (pinfunction "SCL_6") (pintype "input"))
      (node (ref "R3") (pin "2") (pinfunction "2_2") (pintype "passive"))
      (node (ref "SV2") (pin "8") (pinfunction "8_8") (pintype "passive"))
    )
    (net (code "66") (name "SDA") (class "Default")
      (node (ref "IC1") (pin "1") (pinfunction "SDA1/RP9/CN21/PMD3/RB9_1") (pintype "bidirectional"))
      (node (ref "IC2") (pin "5") (pinfunction "SDA_5") (pintype "bidirectional"))
      (node (ref "R7") (pin "2") (pinfunction "2_2") (pintype "passive"))
      (node (ref "SV2") (pin "6") (pinfunction "6_6") (pintype "passive"))
    )
    (net (code "67") (name "TX1") (class "Default")
      (node (ref "IC1") (pin "37") (pinfunction "RP20/CN25/PMA4/RC4_37") (pintype "bidirectional"))
      (node (ref "SV2") (pin "5") (pinfunction "5_5") (pintype "passive"))
    )
    (net (code "68") (name "TX2") (class "Default")
      (node (ref "IC1") (pin "23") (pinfunction "AN4/C1IN-/RP2/CN6/RB2_23") (pintype "bidirectional"))
      (node (ref "SV2") (pin "13") (pinfunction "13_13") (pintype "passive"))
    )
    (net (code "69") (name "VENC") (class "Default")
      (node (ref "J1") (pin "2") (pinfunction "2_2") (pintype "passive"))
      (node (ref "SV1") (pin "3") (pinfunction "3_3") (pintype "passive"))
      (node (ref "SV1") (pin "4") (pinfunction "4_4") (pintype "passive"))
    )
  )
)
